# untitled.net
KiCad netlist of a schematic drawn in EAGLE
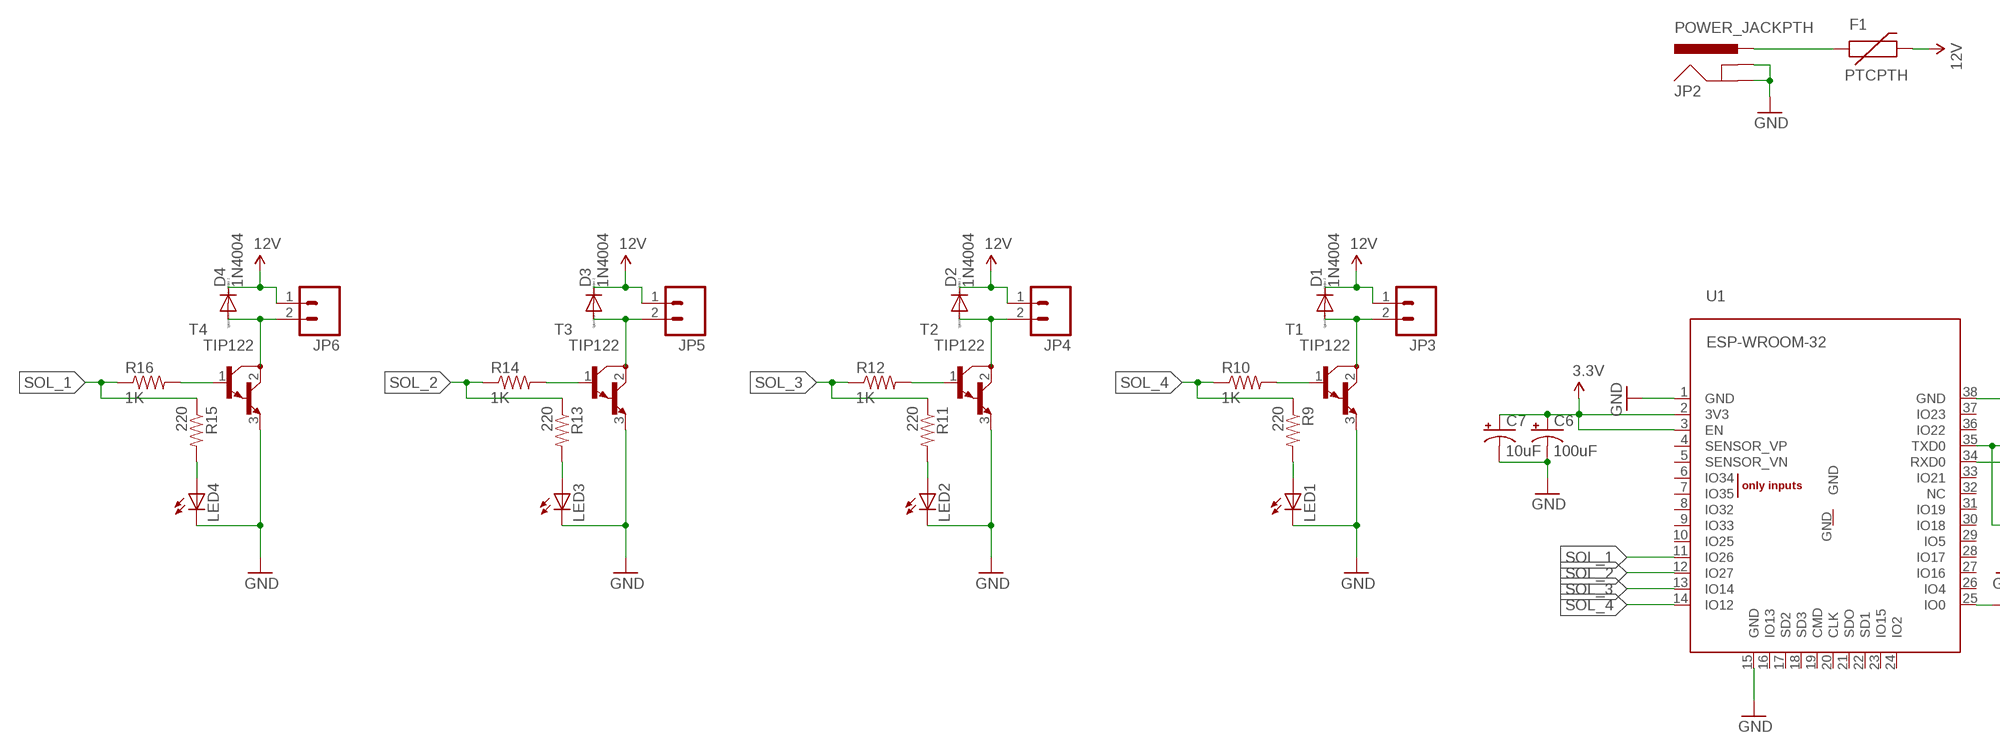
[diagram p0: schematic, sheet 1, part 1 of 2]
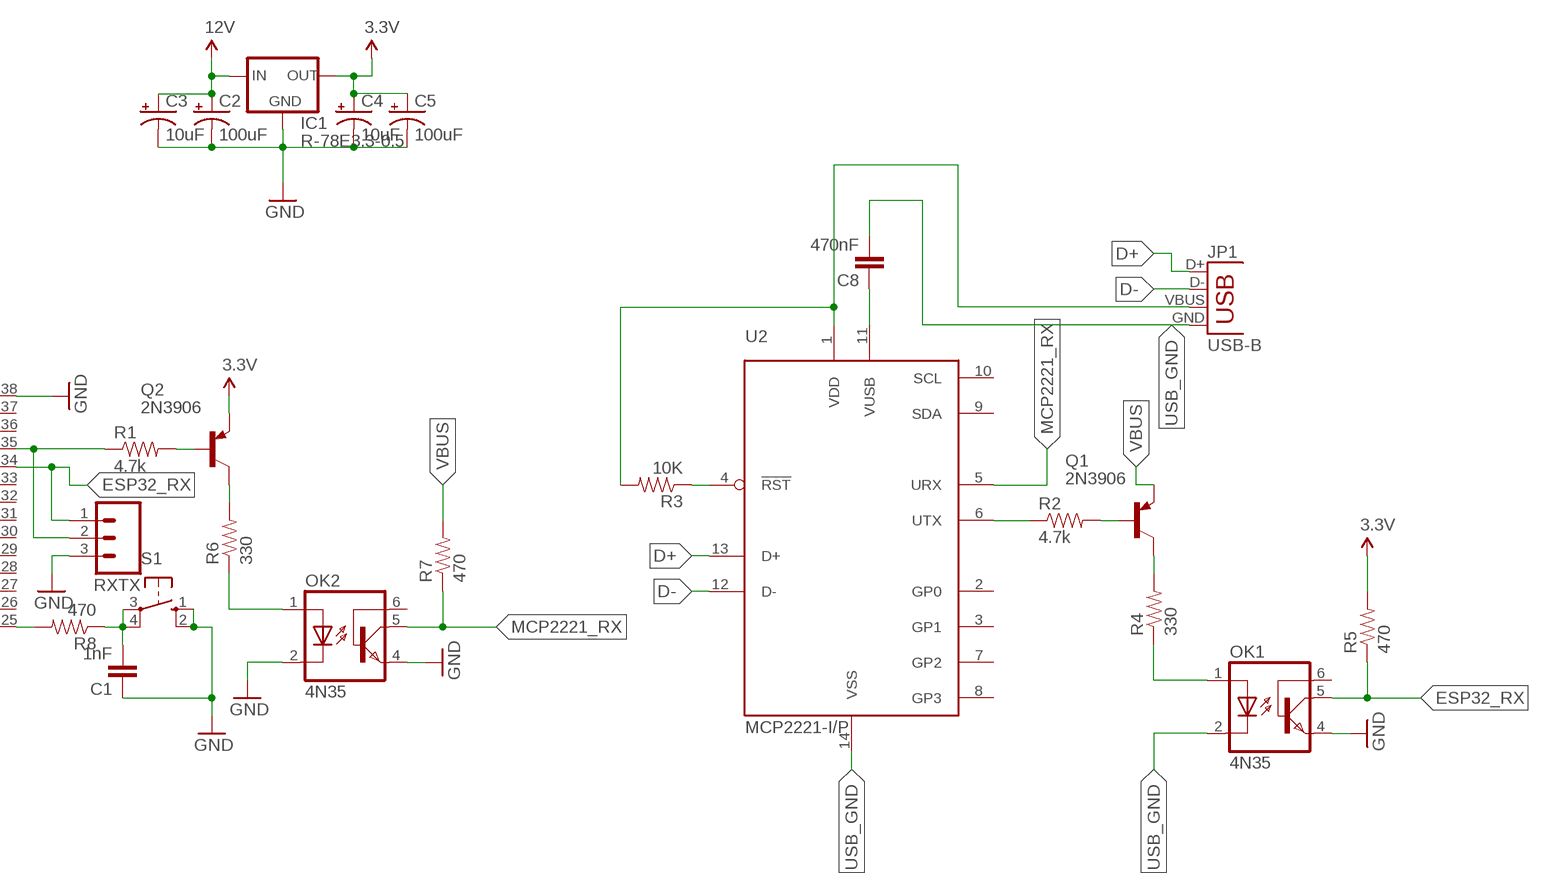
[diagram p1: schematic, sheet 1, part 2 of 2]

(export (version "E")
  (design (tool "Eeschema 10.0.6"))
  (components
    (comp (ref "C1")
      (value "1nF")
      (footprint "eagle-import:CAP-PTH-SMALL-KIT")
      (libsource (lib "eagle-import") (part "CAPKIT"))
    )
    (comp (ref "C2")
      (value "100uF")
      (footprint "eagle-import:CPOL-RADIAL-100UF-25V")
      (libsource (lib "eagle-import") (part "CAP_POLPTH1"))
    )
    (comp (ref "C3")
      (value "10uF")
      (footprint "eagle-import:CPOL-RADIAL-100UF-25V")
      (libsource (lib "eagle-import") (part "CAP_POLPTH1"))
    )
    (comp (ref "C4")
      (value "10uF")
      (footprint "eagle-import:CPOL-RADIAL-100UF-25V")
      (libsource (lib "eagle-import") (part "CAP_POLPTH1"))
    )
    (comp (ref "C5")
      (value "100uF")
      (footprint "eagle-import:CPOL-RADIAL-100UF-25V")
      (libsource (lib "eagle-import") (part "CAP_POLPTH1"))
    )
    (comp (ref "C6")
      (value "100uF")
      (footprint "eagle-import:CPOL-RADIAL-100UF-25V")
      (libsource (lib "eagle-import") (part "CAP_POLPTH1"))
    )
    (comp (ref "C7")
      (value "10uF")
      (footprint "eagle-import:CPOL-RADIAL-100UF-25V")
      (libsource (lib "eagle-import") (part "CAP_POLPTH1"))
    )
    (comp (ref "C8")
      (value "470nF")
      (footprint "eagle-import:CAP-PTH-SMALLEZ")
      (fields (field (name "MF") "MULTICOMP") (field (name "MPN") "MCBU5471K5"))
      (libsource (lib "eagle-import") (part "CAPEZ"))
    )
    (comp (ref "D1")
      (value "1N4004")
      (footprint "eagle-import:DO41-10")
      (libsource (lib "eagle-import") (part "1N4004"))
    )
    (comp (ref "D2")
      (value "1N4004")
      (footprint "eagle-import:DO41-10")
      (libsource (lib "eagle-import") (part "1N4004"))
    )
    (comp (ref "D3")
      (value "1N4004")
      (footprint "eagle-import:DO41-10")
      (libsource (lib "eagle-import") (part "1N4004"))
    )
    (comp (ref "D4")
      (value "1N4004")
      (footprint "eagle-import:DO41-10")
      (libsource (lib "eagle-import") (part "1N4004"))
    )
    (comp (ref "F1")
      (value "PTCPTH")
      (footprint "eagle-import:PTC")
      (libsource (lib "eagle-import") (part "PTCPTH"))
    )
    (comp (ref "IC1")
      (value "R-78E3.3-0.5")
      (footprint "eagle-import:SIP3")
      (fields (field (name "MF") "Recom") (field (name "MPN") "R-783.3-0.5"))
      (libsource (lib "eagle-import") (part "R-78E-0.53.3"))
    )
    (comp (ref "JP1")
      (value "USB-B")
      (footprint "eagle-import:USB-B-PTH")
      (fields (field (name "MF") "MULTICOMP") (field (name "MPN") "USB-B-S-RA."))
      (libsource (lib "eagle-import") (part "USBPTH"))
    )
    (comp (ref "JP2")
      (value "POWER_JACKPTH")
      (footprint "eagle-import:POWER_JACK_PTH")
      (fields (field (name "MF") "CLIFF ELECTRONIC COMPONENTS") (field (name "MPN") "DC10A"))
      (libsource (lib "eagle-import") (part "POWER_JACKPTH"))
    )
    (comp (ref "JP3")
      (value "M02LOCK_LONGPADS")
      (footprint "eagle-import:1X02_LOCK_LONGPADS")
      (libsource (lib "eagle-import") (part "M02LOCK_LONGPADS"))
    )
    (comp (ref "JP4")
      (value "M02LOCK_LONGPADS")
      (footprint "eagle-import:1X02_LOCK_LONGPADS")
      (libsource (lib "eagle-import") (part "M02LOCK_LONGPADS"))
    )
    (comp (ref "JP5")
      (value "M02LOCK_LONGPADS")
      (footprint "eagle-import:1X02_LOCK_LONGPADS")
      (libsource (lib "eagle-import") (part "M02LOCK_LONGPADS"))
    )
    (comp (ref "JP6")
      (value "M02LOCK_LONGPADS")
      (footprint "eagle-import:1X02_LOCK_LONGPADS")
      (libsource (lib "eagle-import") (part "M02LOCK_LONGPADS"))
    )
    (comp (ref "LED1")
      (value "LED3MM")
      (footprint "eagle-import:LED3MM")
      (libsource (lib "eagle-import") (part "LED3MM"))
    )
    (comp (ref "LED2")
      (value "LED3MM")
      (footprint "eagle-import:LED3MM")
      (libsource (lib "eagle-import") (part "LED3MM"))
    )
    (comp (ref "LED3")
      (value "LED3MM")
      (footprint "eagle-import:LED3MM")
      (libsource (lib "eagle-import") (part "LED3MM"))
    )
    (comp (ref "LED4")
      (value "LED3MM")
      (footprint "eagle-import:LED3MM")
      (libsource (lib "eagle-import") (part "LED3MM"))
    )
    (comp (ref "OK1")
      (value "4N35")
      (footprint "eagle-import:DIL06")
      (fields (field (name "MF") "FAIRCHILD SEMICONDUCTOR") (field (name "MF_1") "VISHAY"))
      (libsource (lib "eagle-import") (part "4N35"))
    )
    (comp (ref "OK2")
      (value "4N35")
      (footprint "eagle-import:DIL06")
      (fields (field (name "MF") "FAIRCHILD SEMICONDUCTOR") (field (name "MF_1") "VISHAY"))
      (libsource (lib "eagle-import") (part "4N35"))
    )
    (comp (ref "Q1")
      (value "2N3906")
      (footprint "eagle-import:TO92")
      (fields (field (name "MF") "MULTICOMP"))
      (libsource (lib "eagle-import") (part "2N3906"))
    )
    (comp (ref "Q2")
      (value "2N3906")
      (footprint "eagle-import:TO92")
      (fields (field (name "MF") "MULTICOMP"))
      (libsource (lib "eagle-import") (part "2N3906"))
    )
    (comp (ref "R1")
      (value "4.7k")
      (footprint "eagle-import:AXIAL-0.3")
      (fields (field (name "MF") "MULTICOMP") (field (name "MPN") "MCRE000045"))
      (libsource (lib "eagle-import") (part "RESISTORAXIAL-0.3"))
    )
    (comp (ref "R2")
      (value "4.7k")
      (footprint "eagle-import:AXIAL-0.3")
      (fields (field (name "MF") "MULTICOMP") (field (name "MPN") "MCRE000045"))
      (libsource (lib "eagle-import") (part "RESISTORAXIAL-0.3"))
    )
    (comp (ref "R3")
      (value "10K")
      (footprint "eagle-import:AXIAL-0.3")
      (fields (field (name "MF") "MULTICOMP") (field (name "MPN") "MCMF006FF1002A50"))
      (libsource (lib "eagle-import") (part "RESISTORAXIAL-0.3"))
    )
    (comp (ref "R4")
      (value "330")
      (footprint "eagle-import:AXIAL-0.3")
      (fields (field (name "MF") "MULTICOMP") (field (name "MPN") "MCRE000031"))
      (libsource (lib "eagle-import") (part "RESISTORAXIAL-0.3"))
    )
    (comp (ref "R5")
      (value "470")
      (footprint "eagle-import:AXIAL-0.3")
      (fields (field (name "MF") "MULTICOMP") (field (name "MPN") "MCRE000033"))
      (libsource (lib "eagle-import") (part "RESISTORAXIAL-0.3"))
    )
    (comp (ref "R6")
      (value "330")
      (footprint "eagle-import:AXIAL-0.3")
      (fields (field (name "MF") "MULTICOMP") (field (name "MPN") "MCRE000031"))
      (libsource (lib "eagle-import") (part "RESISTORAXIAL-0.3"))
    )
    (comp (ref "R7")
      (value "470")
      (footprint "eagle-import:AXIAL-0.3")
      (fields (field (name "MF") "MULTICOMP") (field (name "MPN") "MCRE000033"))
      (libsource (lib "eagle-import") (part "RESISTORAXIAL-0.3"))
    )
    (comp (ref "R8")
      (value "470")
      (footprint "eagle-import:AXIAL-0.3")
      (fields (field (name "MF") "MULTICOMP") (field (name "MPN") "MCRE000033"))
      (libsource (lib "eagle-import") (part "RESISTORAXIAL-0.3"))
    )
    (comp (ref "R9")
      (value "220")
      (footprint "eagle-import:AXIAL-0.3")
      (fields (field (name "MF") "MULTICOMP") (field (name "MPN") "MCRE000033"))
      (libsource (lib "eagle-import") (part "RESISTORAXIAL-0.3"))
    )
    (comp (ref "R10")
      (value "1K")
      (footprint "eagle-import:AXIAL-0.3")
      (fields (field (name "MF") "MULTICOMP") (field (name "MPN") "MCRE000033"))
      (libsource (lib "eagle-import") (part "RESISTORAXIAL-0.3"))
    )
    (comp (ref "R11")
      (value "220")
      (footprint "eagle-import:AXIAL-0.3")
      (fields (field (name "MF") "MULTICOMP") (field (name "MPN") "MCRE000033"))
      (libsource (lib "eagle-import") (part "RESISTORAXIAL-0.3"))
    )
    (comp (ref "R12")
      (value "1K")
      (footprint "eagle-import:AXIAL-0.3")
      (fields (field (name "MF") "MULTICOMP") (field (name "MPN") "MCRE000033"))
      (libsource (lib "eagle-import") (part "RESISTORAXIAL-0.3"))
    )
    (comp (ref "R13")
      (value "220")
      (footprint "eagle-import:AXIAL-0.3")
      (fields (field (name "MF") "MULTICOMP") (field (name "MPN") "MCRE000033"))
      (libsource (lib "eagle-import") (part "RESISTORAXIAL-0.3"))
    )
    (comp (ref "R14")
      (value "1K")
      (footprint "eagle-import:AXIAL-0.3")
      (fields (field (name "MF") "MULTICOMP") (field (name "MPN") "MCRE000033"))
      (libsource (lib "eagle-import") (part "RESISTORAXIAL-0.3"))
    )
    (comp (ref "R15")
      (value "220")
      (footprint "eagle-import:AXIAL-0.3")
      (fields (field (name "MF") "MULTICOMP") (field (name "MPN") "MCRE000033"))
      (libsource (lib "eagle-import") (part "RESISTORAXIAL-0.3"))
    )
    (comp (ref "R16")
      (value "1K")
      (footprint "eagle-import:AXIAL-0.3")
      (fields (field (name "MF") "MULTICOMP") (field (name "MPN") "MCRE000033"))
      (libsource (lib "eagle-import") (part "RESISTORAXIAL-0.3"))
    )
    (comp (ref "RXTX")
      (value "M03LONGPADS")
      (footprint "eagle-import:1X03_LONGPADS")
      (libsource (lib "eagle-import") (part "M03LONGPADS"))
    )
    (comp (ref "S1")
      (value "10-XX")
      (footprint "eagle-import:B3F-10XX")
      (fields (field (name "MPN") "B3F-1000"))
      (libsource (lib "eagle-import") (part "10-XX"))
    )
    (comp (ref "T1")
      (value "TIP122")
      (footprint "eagle-import:TO220")
      (libsource (lib "eagle-import") (part "TIP122"))
    )
    (comp (ref "T2")
      (value "TIP122")
      (footprint "eagle-import:TO220")
      (libsource (lib "eagle-import") (part "TIP122"))
    )
    (comp (ref "T3")
      (value "TIP122")
      (footprint "eagle-import:TO220")
      (libsource (lib "eagle-import") (part "TIP122"))
    )
    (comp (ref "T4")
      (value "TIP122")
      (footprint "eagle-import:TO220")
      (libsource (lib "eagle-import") (part "TIP122"))
    )
    (comp (ref "U1")
      (value "ESP-WROOM-32")
      (footprint "eagle-import:ESP-WROOM-32")
      (libsource (lib "eagle-import") (part "ESP-WROOM-32"))
    )
    (comp (ref "U2")
      (value "MCP2221-I/P")
      (footprint "eagle-import:DIL14")
      (fields (field (name "MF") "MICROCHIP"))
      (libsource (lib "eagle-import") (part "MCP2221-I/P"))
    )
  )
  (nets
    (net (code "1") (name "3.3V") (class "Default")
      (node (ref "C4") (pin "1") (pinfunction "+_1") (pintype "passive"))
      (node (ref "C5") (pin "1") (pinfunction "+_1") (pintype "passive"))
      (node (ref "C6") (pin "1") (pinfunction "+_1") (pintype "passive"))
      (node (ref "C7") (pin "1") (pinfunction "+_1") (pintype "passive"))
      (node (ref "IC1") (pin "3") (pinfunction "OUT_3") (pintype "passive"))
      (node (ref "Q2") (pin "3") (pinfunction "E_3") (pintype "passive"))
      (node (ref "R5") (pin "P$2") (pinfunction "2_P$2") (pintype "passive"))
      (node (ref "U1") (pin "2") (pinfunction "3V3_2") (pintype "bidirectional"))
      (node (ref "U1") (pin "3") (pinfunction "EN_3") (pintype "bidirectional"))
    )
    (net (code "2") (name "12V") (class "Default")
      (node (ref "C2") (pin "1") (pinfunction "+_1") (pintype "passive"))
      (node (ref "C3") (pin "1") (pinfunction "+_1") (pintype "passive"))
      (node (ref "D1") (pin "C") (pinfunction "C_C") (pintype "passive"))
      (node (ref "D2") (pin "C") (pinfunction "C_C") (pintype "passive"))
      (node (ref "D3") (pin "C") (pinfunction "C_C") (pintype "passive"))
      (node (ref "D4") (pin "C") (pinfunction "C_C") (pintype "passive"))
      (node (ref "F1") (pin "P$2") (pinfunction "2_P$2") (pintype "bidirectional"))
      (node (ref "IC1") (pin "1") (pinfunction "IN_1") (pintype "input"))
      (node (ref "JP3") (pin "1") (pinfunction "1_1") (pintype "passive"))
      (node (ref "JP4") (pin "1") (pinfunction "1_1") (pintype "passive"))
      (node (ref "JP5") (pin "1") (pinfunction "1_1") (pintype "passive"))
      (node (ref "JP6") (pin "1") (pinfunction "1_1") (pintype "passive"))
    )
    (net (code "3") (name "D+") (class "Default")
      (node (ref "JP1") (pin "D+") (pinfunction "D+_D+") (pintype "bidirectional"))
      (node (ref "U2") (pin "13") (pinfunction "D+_13") (pintype "bidirectional"))
    )
    (net (code "4") (name "D-") (class "Default")
      (node (ref "JP1") (pin "D-") (pinfunction "D-_D-") (pintype "bidirectional"))
      (node (ref "U2") (pin "12") (pinfunction "D-_12") (pintype "bidirectional"))
    )
    (net (code "5") (name "ESP32_RX") (class "Default")
      (node (ref "OK1") (pin "5") (pinfunction "COL_5") (pintype "passive"))
      (node (ref "R5") (pin "P$1") (pinfunction "1_P$1") (pintype "passive"))
      (node (ref "RXTX") (pin "1") (pinfunction "1_1") (pintype "passive"))
      (node (ref "U1") (pin "34") (pinfunction "RXD0_34") (pintype "bidirectional"))
    )
    (net (code "6") (name "GND") (class "Default")
      (node (ref "C1") (pin "1") (pinfunction "1_1") (pintype "passive"))
      (node (ref "C2") (pin "2") (pinfunction "-_2") (pintype "passive"))
      (node (ref "C3") (pin "2") (pinfunction "-_2") (pintype "passive"))
      (node (ref "C4") (pin "2") (pinfunction "-_2") (pintype "passive"))
      (node (ref "C5") (pin "2") (pinfunction "-_2") (pintype "passive"))
      (node (ref "C6") (pin "2") (pinfunction "-_2") (pintype "passive"))
      (node (ref "C7") (pin "2") (pinfunction "-_2") (pintype "passive"))
      (node (ref "IC1") (pin "2") (pinfunction "GND_2") (pintype "input"))
      (node (ref "JP2") (pin "GND") (pinfunction "GND_GND") (pintype "bidirectional"))
      (node (ref "JP2") (pin "GNDBREAK") (pinfunction "GNDBREAK_GNDBREAK") (pintype "bidirectional"))
      (node (ref "LED1") (pin "K") (pinfunction "C_K") (pintype "passive"))
      (node (ref "LED2") (pin "K") (pinfunction "C_K") (pintype "passive"))
      (node (ref "LED3") (pin "K") (pinfunction "C_K") (pintype "passive"))
      (node (ref "LED4") (pin "K") (pinfunction "C_K") (pintype "passive"))
      (node (ref "OK1") (pin "4") (pinfunction "EMI_4") (pintype "passive"))
      (node (ref "OK2") (pin "2") (pinfunction "C_2") (pintype "passive"))
      (node (ref "OK2") (pin "4") (pinfunction "EMI_4") (pintype "passive"))
      (node (ref "RXTX") (pin "3") (pinfunction "3_3") (pintype "passive"))
      (node (ref "S1") (pin "1") (pinfunction "S_1") (pintype "passive"))
      (node (ref "S1") (pin "2") (pinfunction "S1_2") (pintype "passive"))
      (node (ref "T1") (pin "3") (pinfunction "E_3") (pintype "passive"))
      (node (ref "T2") (pin "3") (pinfunction "E_3") (pintype "passive"))
      (node (ref "T3") (pin "3") (pinfunction "E_3") (pintype "passive"))
      (node (ref "T4") (pin "3") (pinfunction "E_3") (pintype "passive"))
      (node (ref "U1") (pin "1") (pinfunction "GND_1") (pintype "bidirectional"))
      (node (ref "U1") (pin "15") (pinfunction "GND_15") (pintype "bidirectional"))
      (node (ref "U1") (pin "38") (pinfunction "GND_38") (pintype "bidirectional"))
    )
    (net (code "7") (name "MCP2221_RX") (class "Default")
      (node (ref "OK2") (pin "5") (pinfunction "COL_5") (pintype "passive"))
      (node (ref "R7") (pin "P$1") (pinfunction "1_P$1") (pintype "passive"))
      (node (ref "U2") (pin "5") (pinfunction "URX_5") (pintype "input"))
    )
    (net (code "8") (name "Net-(F1-1)") (class "Default")
      (node (ref "F1") (pin "P$1") (pinfunction "1_P$1") (pintype "bidirectional"))
      (node (ref "JP2") (pin "PWR") (pinfunction "PWR_PWR") (pintype "bidirectional"))
    )
    (net (code "9") (name "Net-(OK1-A)") (class "Default")
      (node (ref "OK1") (pin "1") (pinfunction "A_1") (pintype "passive"))
      (node (ref "R4") (pin "P$1") (pinfunction "1_P$1") (pintype "passive"))
    )
    (net (code "10") (name "Net-(OK2-A)") (class "Default")
      (node (ref "OK2") (pin "1") (pinfunction "A_1") (pintype "passive"))
      (node (ref "R6") (pin "P$1") (pinfunction "1_P$1") (pintype "passive"))
    )
    (net (code "11") (name "Net-(Q1-B)") (class "Default")
      (node (ref "Q1") (pin "2") (pinfunction "B_2") (pintype "passive"))
      (node (ref "R2") (pin "P$2") (pinfunction "2_P$2") (pintype "passive"))
    )
    (net (code "12") (name "Net-(Q1-C)") (class "Default")
      (node (ref "Q1") (pin "1") (pinfunction "C_1") (pintype "passive"))
      (node (ref "R4") (pin "P$2") (pinfunction "2_P$2") (pintype "passive"))
    )
    (net (code "13") (name "Net-(Q2-B)") (class "Default")
      (node (ref "Q2") (pin "2") (pinfunction "B_2") (pintype "passive"))
      (node (ref "R1") (pin "P$2") (pinfunction "2_P$2") (pintype "passive"))
    )
    (net (code "14") (name "Net-(Q2-C)") (class "Default")
      (node (ref "Q2") (pin "1") (pinfunction "C_1") (pintype "passive"))
      (node (ref "R6") (pin "P$2") (pinfunction "2_P$2") (pintype "passive"))
    )
    (net (code "15") (name "Net-(R1-1)") (class "Default")
      (node (ref "R1") (pin "P$1") (pinfunction "1_P$1") (pintype "passive"))
      (node (ref "RXTX") (pin "2") (pinfunction "2_2") (pintype "passive"))
      (node (ref "U1") (pin "35") (pinfunction "TXD0_35") (pintype "bidirectional"))
    )
    (net (code "16") (name "Net-(R2-1)") (class "Default")
      (node (ref "R2") (pin "P$1") (pinfunction "1_P$1") (pintype "passive"))
      (node (ref "U2") (pin "6") (pinfunction "UTX_6") (pintype "output"))
    )
    (net (code "17") (name "Net-(R3-1)") (class "Default")
      (node (ref "R3") (pin "P$1") (pinfunction "1_P$1") (pintype "passive"))
      (node (ref "U2") (pin "4") (pinfunction "~{RST}_4") (pintype "input"))
    )
    (net (code "18") (name "Net-(R8-1)") (class "Default")
      (node (ref "C1") (pin "2") (pinfunction "2_2") (pintype "passive"))
      (node (ref "R8") (pin "P$1") (pinfunction "1_P$1") (pintype "passive"))
      (node (ref "S1") (pin "3") (pinfunction "P_3") (pintype "passive"))
      (node (ref "S1") (pin "4") (pinfunction "P1_4") (pintype "passive"))
    )
    (net (code "19") (name "Net-(R8-2)") (class "Default")
      (node (ref "R8") (pin "P$2") (pinfunction "2_P$2") (pintype "passive"))
      (node (ref "U1") (pin "25") (pinfunction "IO0_25") (pintype "bidirectional"))
    )
    (net (code "20") (name "Net-(R9-2)") (class "Default")
      (node (ref "LED1") (pin "A") (pinfunction "A_A") (pintype "passive"))
      (node (ref "R9") (pin "P$2") (pinfunction "2_P$2") (pintype "passive"))
    )
    (net (code "21") (name "Net-(R10-2)") (class "Default")
      (node (ref "R10") (pin "P$2") (pinfunction "2_P$2") (pintype "passive"))
      (node (ref "T1") (pin "1") (pinfunction "B_1") (pintype "passive"))
    )
    (net (code "22") (name "Net-(R11-2)") (class "Default")
      (node (ref "LED2") (pin "A") (pinfunction "A_A") (pintype "passive"))
      (node (ref "R11") (pin "P$2") (pinfunction "2_P$2") (pintype "passive"))
    )
    (net (code "23") (name "Net-(R12-2)") (class "Default")
      (node (ref "R12") (pin "P$2") (pinfunction "2_P$2") (pintype "passive"))
      (node (ref "T2") (pin "1") (pinfunction "B_1") (pintype "passive"))
    )
    (net (code "24") (name "Net-(R13-2)") (class "Default")
      (node (ref "LED3") (pin "A") (pinfunction "A_A") (pintype "passive"))
      (node (ref "R13") (pin "P$2") (pinfunction "2_P$2") (pintype "passive"))
    )
    (net (code "25") (name "Net-(R14-2)") (class "Default")
      (node (ref "R14") (pin "P$2") (pinfunction "2_P$2") (pintype "passive"))
      (node (ref "T3") (pin "1") (pinfunction "B_1") (pintype "passive"))
    )
    (net (code "26") (name "Net-(R15-2)") (class "Default")
      (node (ref "LED4") (pin "A") (pinfunction "A_A") (pintype "passive"))
      (node (ref "R15") (pin "P$2") (pinfunction "2_P$2") (pintype "passive"))
    )
    (net (code "27") (name "Net-(R16-2)") (class "Default")
      (node (ref "R16") (pin "P$2") (pinfunction "2_P$2") (pintype "passive"))
      (node (ref "T4") (pin "1") (pinfunction "B_1") (pintype "passive"))
    )
    (net (code "28") (name "Net-(T1-C)") (class "Default")
      (node (ref "D1") (pin "A") (pinfunction "A_A") (pintype "passive"))
      (node (ref "JP3") (pin "2") (pinfunction "2_2") (pintype "passive"))
      (node (ref "T1") (pin "2") (pinfunction "C_2") (pintype "passive"))
    )
    (net (code "29") (name "Net-(T2-C)") (class "Default")
      (node (ref "D2") (pin "A") (pinfunction "A_A") (pintype "passive"))
      (node (ref "JP4") (pin "2") (pinfunction "2_2") (pintype "passive"))
      (node (ref "T2") (pin "2") (pinfunction "C_2") (pintype "passive"))
    )
    (net (code "30") (name "Net-(T3-C)") (class "Default")
      (node (ref "D3") (pin "A") (pinfunction "A_A") (pintype "passive"))
      (node (ref "JP5") (pin "2") (pinfunction "2_2") (pintype "passive"))
      (node (ref "T3") (pin "2") (pinfunction "C_2") (pintype "passive"))
    )
    (net (code "31") (name "Net-(T4-C)") (class "Default")
      (node (ref "D4") (pin "A") (pinfunction "A_A") (pintype "passive"))
      (node (ref "JP6") (pin "2") (pinfunction "2_2") (pintype "passive"))
      (node (ref "T4") (pin "2") (pinfunction "C_2") (pintype "passive"))
    )
    (net (code "32") (name "Net-(U2-VUSB)") (class "Default")
      (node (ref "C8") (pin "1") (pinfunction "1_1") (pintype "passive"))
      (node (ref "U2") (pin "11") (pinfunction "VUSB_11") (pintype "power_in"))
    )
    (net (code "33") (name "SOL_1") (class "Default")
      (node (ref "R15") (pin "P$1") (pinfunction "1_P$1") (pintype "passive"))
      (node (ref "R16") (pin "P$1") (pinfunction "1_P$1") (pintype "passive"))
      (node (ref "U1") (pin "11") (pinfunction "IO26_11") (pintype "bidirectional"))
    )
    (net (code "34") (name "SOL_2") (class "Default")
      (node (ref "R13") (pin "P$1") (pinfunction "1_P$1") (pintype "passive"))
      (node (ref "R14") (pin "P$1") (pinfunction "1_P$1") (pintype "passive"))
      (node (ref "U1") (pin "12") (pinfunction "IO27_12") (pintype "bidirectional"))
    )
    (net (code "35") (name "SOL_3") (class "Default")
      (node (ref "R11") (pin "P$1") (pinfunction "1_P$1") (pintype "passive"))
      (node (ref "R12") (pin "P$1") (pinfunction "1_P$1") (pintype "passive"))
      (node (ref "U1") (pin "13") (pinfunction "IO14_13") (pintype "bidirectional"))
    )
    (net (code "36") (name "SOL_4") (class "Default")
      (node (ref "R10") (pin "P$1") (pinfunction "1_P$1") (pintype "passive"))
      (node (ref "R9") (pin "P$1") (pinfunction "1_P$1") (pintype "passive"))
      (node (ref "U1") (pin "14") (pinfunction "IO12_14") (pintype "bidirectional"))
    )
    (net (code "37") (name "USB_GND") (class "Default")
      (node (ref "C8") (pin "2") (pinfunction "2_2") (pintype "passive"))
      (node (ref "JP1") (pin "GND") (pinfunction "GND_GND") (pintype "bidirectional"))
      (node (ref "OK1") (pin "2") (pinfunction "C_2") (pintype "passive"))
      (node (ref "U2") (pin "14") (pinfunction "VSS_14") (pintype "power_in"))
    )
    (net (code "38") (name "VBUS") (class "Default")
      (node (ref "JP1") (pin "VBUS") (pinfunction "VBUS_VBUS") (pintype "bidirectional"))
      (node (ref "Q1") (pin "3") (pinfunction "E_3") (pintype "passive"))
      (node (ref "R3") (pin "P$2") (pinfunction "2_P$2") (pintype "passive"))
      (node (ref "R7") (pin "P$2") (pinfunction "2_P$2") (pintype "passive"))
      (node (ref "U2") (pin "1") (pinfunction "VDD_1") (pintype "power_in"))
    )
    (net (code "39") (name "unconnected-(OK1-BAS-Pad6)") (class "Default")
      (node (ref "OK1") (pin "6") (pinfunction "BAS_6") (pintype "passive"))
    )
    (net (code "40") (name "unconnected-(OK2-BAS-Pad6)") (class "Default")
      (node (ref "OK2") (pin "6") (pinfunction "BAS_6") (pintype "passive"))
    )
    (net (code "41") (name "unconnected-(U1-CLK-Pad20)") (class "Default")
      (node (ref "U1") (pin "20") (pinfunction "CLK_20") (pintype "bidirectional"))
    )
    (net (code "42") (name "unconnected-(U1-CMD-Pad19)") (class "Default")
      (node (ref "U1") (pin "19") (pinfunction "CMD_19") (pintype "bidirectional"))
    )
    (net (code "43") (name "unconnected-(U1-IO2-Pad24)") (class "Default")
      (node (ref "U1") (pin "24") (pinfunction "IO2_24") (pintype "bidirectional"))
    )
    (net (code "44") (name "unconnected-(U1-IO4-Pad26)") (class "Default")
      (node (ref "U1") (pin "26") (pinfunction "IO4_26") (pintype "bidirectional"))
    )
    (net (code "45") (name "unconnected-(U1-IO5-Pad29)") (class "Default")
      (node (ref "U1") (pin "29") (pinfunction "IO5_29") (pintype "bidirectional"))
    )
    (net (code "46") (name "unconnected-(U1-IO13-Pad16)") (class "Default")
      (node (ref "U1") (pin "16") (pinfunction "IO13_16") (pintype "bidirectional"))
    )
    (net (code "47") (name "unconnected-(U1-IO15-Pad23)") (class "Default")
      (node (ref "U1") (pin "23") (pinfunction "IO15_23") (pintype "bidirectional"))
    )
    (net (code "48") (name "unconnected-(U1-IO16-Pad27)") (class "Default")
      (node (ref "U1") (pin "27") (pinfunction "IO16_27") (pintype "bidirectional"))
    )
    (net (code "49") (name "unconnected-(U1-IO17-Pad28)") (class "Default")
      (node (ref "U1") (pin "28") (pinfunction "IO17_28") (pintype "bidirectional"))
    )
    (net (code "50") (name "unconnected-(U1-IO18-Pad30)") (class "Default")
      (node (ref "U1") (pin "30") (pinfunction "IO18_30") (pintype "bidirectional"))
    )
    (net (code "51") (name "unconnected-(U1-IO19-Pad31)") (class "Default")
      (node (ref "U1") (pin "31") (pinfunction "IO19_31") (pintype "bidirectional"))
    )
    (net (code "52") (name "unconnected-(U1-IO21-Pad33)") (class "Default")
      (node (ref "U1") (pin "33") (pinfunction "IO21_33") (pintype "bidirectional"))
    )
    (net (code "53") (name "unconnected-(U1-IO22-Pad36)") (class "Default")
      (node (ref "U1") (pin "36") (pinfunction "IO22_36") (pintype "bidirectional"))
    )
    (net (code "54") (name "unconnected-(U1-IO23-Pad37)") (class "Default")
      (node (ref "U1") (pin "37") (pinfunction "IO23_37") (pintype "bidirectional"))
    )
    (net (code "55") (name "unconnected-(U1-IO25-Pad10)") (class "Default")
      (node (ref "U1") (pin "10") (pinfunction "IO25_10") (pintype "bidirectional"))
    )
    (net (code "56") (name "unconnected-(U1-IO32-Pad8)") (class "Default")
      (node (ref "U1") (pin "8") (pinfunction "IO32_8") (pintype "bidirectional"))
    )
    (net (code "57") (name "unconnected-(U1-IO33-Pad9)") (class "Default")
      (node (ref "U1") (pin "9") (pinfunction "IO33_9") (pintype "bidirectional"))
    )
    (net (code "58") (name "unconnected-(U1-IO34-Pad6)") (class "Default")
      (node (ref "U1") (pin "6") (pinfunction "IO34_6") (pintype "input"))
    )
    (net (code "59") (name "unconnected-(U1-IO35-Pad7)") (class "Default")
      (node (ref "U1") (pin "7") (pinfunction "IO35_7") (pintype "input"))
    )
    (net (code "60") (name "unconnected-(U1-NC-Pad32)") (class "Default")
      (node (ref "U1") (pin "32") (pinfunction "NC_32") (pintype "bidirectional"))
    )
    (net (code "61") (name "unconnected-(U1-PadGND)") (class "Default")
      (node (ref "U1") (pin "GND") (pinfunction "GND_GND") (pintype "bidirectional"))
    )
    (net (code "62") (name "unconnected-(U1-SD1-Pad22)") (class "Default")
      (node (ref "U1") (pin "22") (pinfunction "SD1_22") (pintype "bidirectional"))
    )
    (net (code "63") (name "unconnected-(U1-SD2-Pad17)") (class "Default")
      (node (ref "U1") (pin "17") (pinfunction "SD2_17") (pintype "bidirectional"))
    )
    (net (code "64") (name "unconnected-(U1-SD3-Pad18)") (class "Default")
      (node (ref "U1") (pin "18") (pinfunction "SD3_18") (pintype "bidirectional"))
    )
    (net (code "65") (name "unconnected-(U1-SDO-Pad21)") (class "Default")
      (node (ref "U1") (pin "21") (pinfunction "SDO_21") (pintype "bidirectional"))
    )
    (net (code "66") (name "unconnected-(U1-SENSOR_VN-Pad5)") (class "Default")
      (node (ref "U1") (pin "5") (pinfunction "SENSOR_VN_5") (pintype "input"))
    )
    (net (code "67") (name "unconnected-(U1-SENSOR_VP-Pad4)") (class "Default")
      (node (ref "U1") (pin "4") (pinfunction "SENSOR_VP_4") (pintype "input"))
    )
    (net (code "68") (name "unconnected-(U2-GP0-Pad2)") (class "Default")
      (node (ref "U2") (pin "2") (pinfunction "GP0_2") (pintype "bidirectional"))
    )
    (net (code "69") (name "unconnected-(U2-GP1-Pad3)") (class "Default")
      (node (ref "U2") (pin "3") (pinfunction "GP1_3") (pintype "bidirectional"))
    )
    (net (code "70") (name "unconnected-(U2-GP2-Pad7)") (class "Default")
      (node (ref "U2") (pin "7") (pinfunction "GP2_7") (pintype "bidirectional"))
    )
    (net (code "71") (name "unconnected-(U2-GP3-Pad8)") (class "Default")
      (node (ref "U2") (pin "8") (pinfunction "GP3_8") (pintype "bidirectional"))
    )
    (net (code "72") (name "unconnected-(U2-SCL-Pad10)") (class "Default")
      (node (ref "U2") (pin "10") (pinfunction "SCL_10") (pintype "output"))
    )
    (net (code "73") (name "unconnected-(U2-SDA-Pad9)") (class "Default")
      (node (ref "U2") (pin "9") (pinfunction "SDA_9") (pintype "bidirectional"))
    )
  )
)
